# DAC_Output.net
KiCad netlist of a schematic drawn in Altium Designer
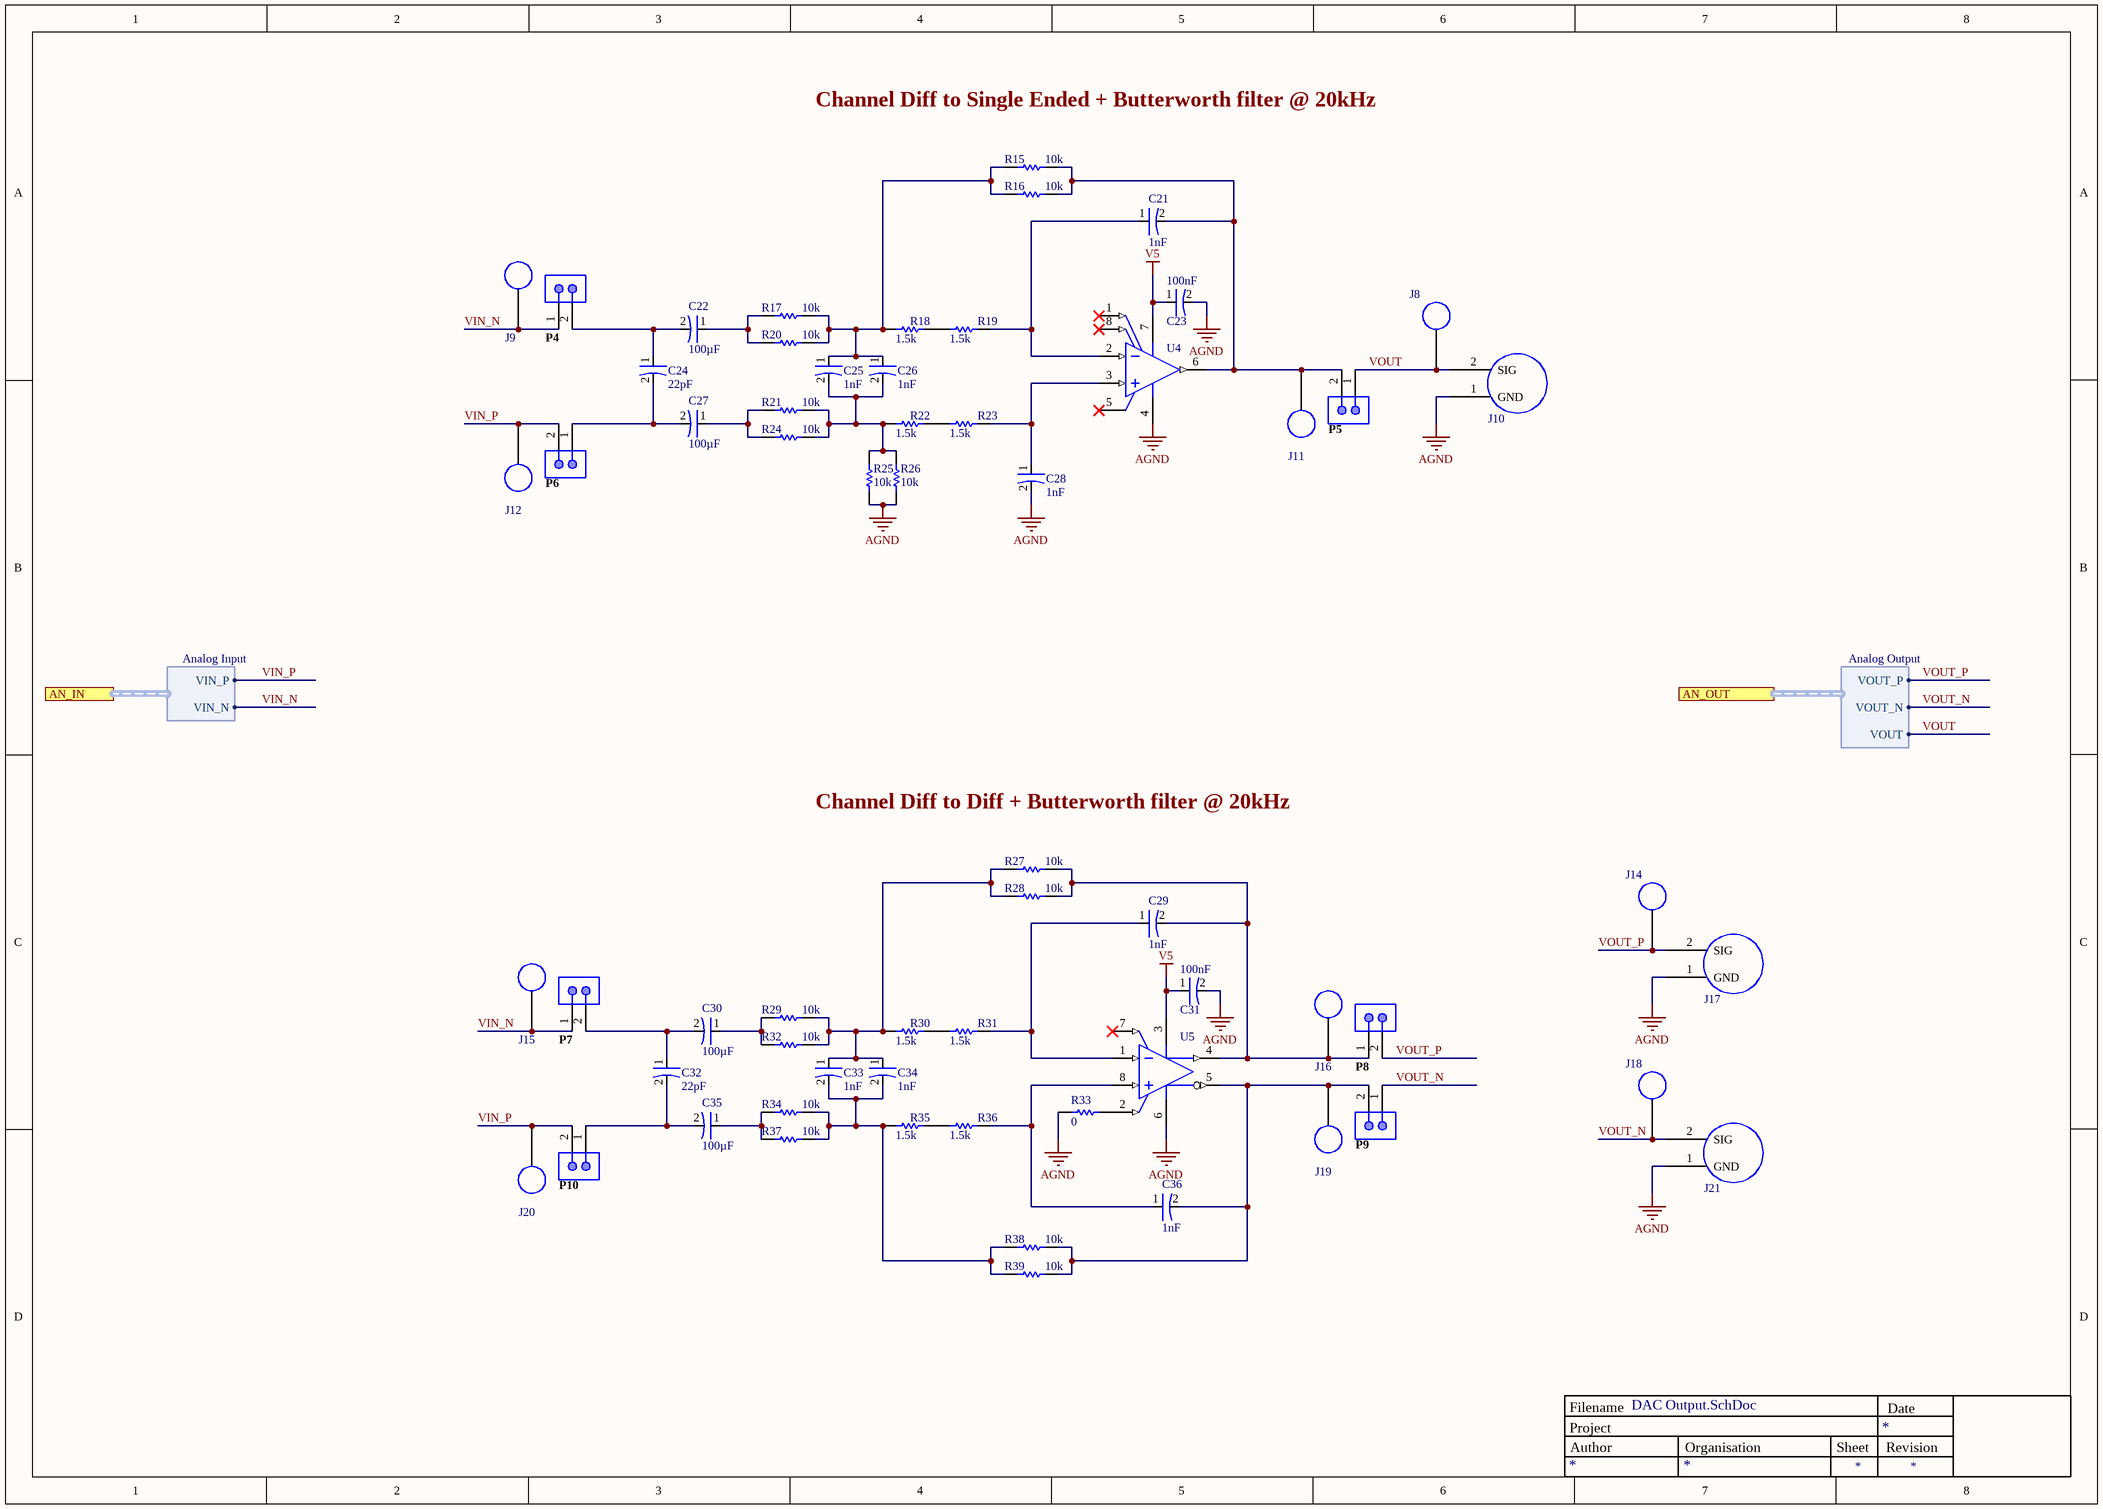
[diagram p0: DAC Output.SchDoc]

(export (version "E")
  (design (tool "Eeschema 10.0.6"))
  (components
    (comp (ref "C21")
      (value "1nF")
      (footprint "0402-M")
      (description "CAP-1nF-CER-0402-50V-X5R-10%")
      (fields (field (name "MANUFACTURER") "Generic") (field (name "Comment") "CAP 1nF CER 0402 50V X5R 10%"))
      (libsource (lib "") (part "Symbol_1"))
    )
    (comp (ref "C22")
      (value "100µF")
      (footprint "1210-M")
      (description "CAP-100uF-CER-1210-16V-X5R-20%")
      (fields
        (field (name "MANUFACTURER") "Generic")
        (field (name "Comment") "CAP 100uF CER 1210 16V X5R 20%")
      )
      (libsource (lib "") (part "Symbol_1"))
    )
    (comp (ref "C23")
      (value "100nF")
      (footprint "0805-M")
      (description "CAP-0.1uF-CER-0805-50V- X7R-5%")
      (fields
        (field (name "MANUFACTURER") "Generic")
        (field (name "Comment") "CAP 0.1uF CER 0805 50V  X7R 5%")
      )
      (libsource (lib "") (part "Symbol_1"))
    )
    (comp (ref "C24")
      (value "22pF")
      (footprint "0805-M")
      (description "CAP 22pF CER 0805 50V C0G 2%")
      (fields (field (name "MANUFACTURER") "Generic"))
      (libsource (lib "") (part "Symbol_1"))
    )
    (comp (ref "C25")
      (value "1nF")
      (footprint "0402-M")
      (description "CAP-1nF-CER-0402-50V-X5R-10%")
      (fields (field (name "MANUFACTURER") "Generic") (field (name "Comment") "CAP 1nF CER 0402 50V X5R 10%"))
      (libsource (lib "") (part "Symbol_1"))
    )
    (comp (ref "C26")
      (value "1nF")
      (footprint "0402-M")
      (description "CAP-1nF-CER-0402-50V-X5R-10%")
      (fields (field (name "MANUFACTURER") "Generic") (field (name "Comment") "CAP 1nF CER 0402 50V X5R 10%"))
      (libsource (lib "") (part "Symbol_1"))
    )
    (comp (ref "C27")
      (value "100µF")
      (footprint "1210-M")
      (description "CAP-100uF-CER-1210-16V-X5R-20%")
      (fields
        (field (name "MANUFACTURER") "Generic")
        (field (name "Comment") "CAP 100uF CER 1210 16V X5R 20%")
      )
      (libsource (lib "") (part "Symbol_1"))
    )
    (comp (ref "C28")
      (value "1nF")
      (footprint "0402-M")
      (description "CAP-1nF-CER-0402-50V-X5R-10%")
      (fields (field (name "MANUFACTURER") "Generic") (field (name "Comment") "CAP 1nF CER 0402 50V X5R 10%"))
      (libsource (lib "") (part "Symbol_1"))
    )
    (comp (ref "C29")
      (value "1nF")
      (footprint "0402-M")
      (description "CAP-1nF-CER-0402-50V-X5R-10%")
      (fields (field (name "MANUFACTURER") "Generic") (field (name "Comment") "CAP 1nF CER 0402 50V X5R 10%"))
      (libsource (lib "") (part "Symbol_1"))
    )
    (comp (ref "C30")
      (value "100µF")
      (footprint "1210-M")
      (description "CAP-100uF-CER-1210-16V-X5R-20%")
      (fields
        (field (name "MANUFACTURER") "Generic")
        (field (name "Comment") "CAP 100uF CER 1210 16V X5R 20%")
      )
      (libsource (lib "") (part "Symbol_1"))
    )
    (comp (ref "C31")
      (value "100nF")
      (footprint "0805-M")
      (description "CAP-0.1uF-CER-0805-50V- X7R-5%")
      (fields
        (field (name "MANUFACTURER") "Generic")
        (field (name "Comment") "CAP 0.1uF CER 0805 50V  X7R 5%")
      )
      (libsource (lib "") (part "Symbol_1"))
    )
    (comp (ref "C32")
      (value "22pF")
      (footprint "0805-M")
      (description "CAP 22pF CER 0805 50V C0G 2%")
      (fields (field (name "MANUFACTURER") "Generic"))
      (libsource (lib "") (part "Symbol_1"))
    )
    (comp (ref "C33")
      (value "1nF")
      (footprint "0402-M")
      (description "CAP-1nF-CER-0402-50V-X5R-10%")
      (fields (field (name "MANUFACTURER") "Generic") (field (name "Comment") "CAP 1nF CER 0402 50V X5R 10%"))
      (libsource (lib "") (part "Symbol_1"))
    )
    (comp (ref "C34")
      (value "1nF")
      (footprint "0402-M")
      (description "CAP-1nF-CER-0402-50V-X5R-10%")
      (fields (field (name "MANUFACTURER") "Generic") (field (name "Comment") "CAP 1nF CER 0402 50V X5R 10%"))
      (libsource (lib "") (part "Symbol_1"))
    )
    (comp (ref "C35")
      (value "100µF")
      (footprint "1210-M")
      (description "CAP-100uF-CER-1210-16V-X5R-20%")
      (fields
        (field (name "MANUFACTURER") "Generic")
        (field (name "Comment") "CAP 100uF CER 1210 16V X5R 20%")
      )
      (libsource (lib "") (part "Symbol_1"))
    )
    (comp (ref "C36")
      (value "1nF")
      (footprint "0402-M")
      (description "CAP-1nF-CER-0402-50V-X5R-10%")
      (fields (field (name "MANUFACTURER") "Generic") (field (name "Comment") "CAP 1nF CER 0402 50V X5R 10%"))
      (libsource (lib "") (part "Symbol_1"))
    )
    (comp (ref "J8")
      (value "151-203-RC")
      (footprint "151-203-RC-Footprint-1")
      (description "PCB-Probe-Ring")
      (libsource (lib "University of Malta - MEMENTO") (part "PCB Probe Ring"))
    )
    (comp (ref "J9")
      (value "151-203-RC")
      (footprint "151-203-RC-Footprint-1")
      (description "PCB-Probe-Ring")
      (libsource (lib "University of Malta - MEMENTO") (part "PCB Probe Ring"))
    )
    (comp (ref "J10")
      (value "SMA CONNECTOR")
      (footprint "SMA CONNECTOR-Footprint-1")
      (fields (field (name "MANUFACTURER") "LPRS"))
      (libsource (lib "University of Malta - MEMENTO") (part "SMA CONNECTOR"))
    )
    (comp (ref "J11")
      (value "151-203-RC")
      (footprint "151-203-RC-Footprint-1")
      (description "PCB-Probe-Ring")
      (libsource (lib "University of Malta - MEMENTO") (part "PCB Probe Ring"))
    )
    (comp (ref "J12")
      (value "151-203-RC")
      (footprint "151-203-RC-Footprint-1")
      (description "PCB-Probe-Ring")
      (libsource (lib "University of Malta - MEMENTO") (part "PCB Probe Ring"))
    )
    (comp (ref "J14")
      (value "151-203-RC")
      (footprint "151-203-RC-Footprint-1")
      (description "PCB-Probe-Ring")
      (libsource (lib "University of Malta - MEMENTO") (part "PCB Probe Ring"))
    )
    (comp (ref "J15")
      (value "151-203-RC")
      (footprint "151-203-RC-Footprint-1")
      (description "PCB-Probe-Ring")
      (libsource (lib "University of Malta - MEMENTO") (part "PCB Probe Ring"))
    )
    (comp (ref "J16")
      (value "151-203-RC")
      (footprint "151-203-RC-Footprint-1")
      (description "PCB-Probe-Ring")
      (libsource (lib "University of Malta - MEMENTO") (part "PCB Probe Ring"))
    )
    (comp (ref "J17")
      (value "SMA CONNECTOR")
      (footprint "SMA CONNECTOR-Footprint-1")
      (fields (field (name "MANUFACTURER") "LPRS"))
      (libsource (lib "University of Malta - MEMENTO") (part "SMA CONNECTOR"))
    )
    (comp (ref "J18")
      (value "151-203-RC")
      (footprint "151-203-RC-Footprint-1")
      (description "PCB-Probe-Ring")
      (libsource (lib "University of Malta - MEMENTO") (part "PCB Probe Ring"))
    )
    (comp (ref "J19")
      (value "151-203-RC")
      (footprint "151-203-RC-Footprint-1")
      (description "PCB-Probe-Ring")
      (libsource (lib "University of Malta - MEMENTO") (part "PCB Probe Ring"))
    )
    (comp (ref "J20")
      (value "151-203-RC")
      (footprint "151-203-RC-Footprint-1")
      (description "PCB-Probe-Ring")
      (libsource (lib "University of Malta - MEMENTO") (part "PCB Probe Ring"))
    )
    (comp (ref "J21")
      (value "SMA CONNECTOR")
      (footprint "SMA CONNECTOR-Footprint-1")
      (fields (field (name "MANUFACTURER") "LPRS"))
      (libsource (lib "University of Malta - MEMENTO") (part "SMA CONNECTOR"))
    )
    (comp (ref "P4")
      (value "GENERIC 2PIN HEADER MALE")
      (footprint "GENERIC 2PIN HEADER 0")
      (description "CONN MAL TH 2 0Deg HEADER")
      (fields (field (name "MANUFACTURER") "Generic"))
      (libsource (lib "") (part "GENERIC 2PIN HEADER MALE_1"))
    )
    (comp (ref "P5")
      (value "GENERIC 2PIN HEADER MALE")
      (footprint "GENERIC 2PIN HEADER 0")
      (description "CONN MAL TH 2 0Deg HEADER")
      (fields (field (name "MANUFACTURER") "Generic"))
      (libsource (lib "University of Malta - MEMENTO") (part "GENERIC 2PIN HEADER MALE"))
    )
    (comp (ref "P6")
      (value "GENERIC 2PIN HEADER MALE")
      (footprint "GENERIC 2PIN HEADER 0")
      (description "CONN MAL TH 2 0Deg HEADER")
      (fields (field (name "MANUFACTURER") "Generic"))
      (libsource (lib "University of Malta - MEMENTO") (part "GENERIC 2PIN HEADER MALE"))
    )
    (comp (ref "P7")
      (value "GENERIC 2PIN HEADER MALE")
      (footprint "GENERIC 2PIN HEADER 0")
      (description "CONN MAL TH 2 0Deg HEADER")
      (fields (field (name "MANUFACTURER") "Generic"))
      (libsource (lib "") (part "GENERIC 2PIN HEADER MALE_1"))
    )
    (comp (ref "P8")
      (value "GENERIC 2PIN HEADER MALE")
      (footprint "GENERIC 2PIN HEADER 0")
      (description "CONN MAL TH 2 0Deg HEADER")
      (fields (field (name "MANUFACTURER") "Generic"))
      (libsource (lib "") (part "GENERIC 2PIN HEADER MALE_1"))
    )
    (comp (ref "P9")
      (value "GENERIC 2PIN HEADER MALE")
      (footprint "GENERIC 2PIN HEADER 0")
      (description "CONN MAL TH 2 0Deg HEADER")
      (fields (field (name "MANUFACTURER") "Generic"))
      (libsource (lib "University of Malta - MEMENTO") (part "GENERIC 2PIN HEADER MALE"))
    )
    (comp (ref "P10")
      (value "GENERIC 2PIN HEADER MALE")
      (footprint "GENERIC 2PIN HEADER 0")
      (description "CONN MAL TH 2 0Deg HEADER")
      (fields (field (name "MANUFACTURER") "Generic"))
      (libsource (lib "University of Malta - MEMENTO") (part "GENERIC 2PIN HEADER MALE"))
    )
    (comp (ref "R15")
      (value "10k")
      (footprint "0805-M")
      (description "RES-10k-0805-125mW-1%")
      (fields (field (name "MANUFACTURER") "Generic") (field (name "Comment") "RES 10k 0805 125mW 1%"))
      (libsource (lib "University of Malta - MEMENTO") (part "Symbol"))
    )
    (comp (ref "R16")
      (value "10k")
      (footprint "0805-M")
      (description "RES-10k-0805-125mW-1%")
      (fields (field (name "MANUFACTURER") "Generic") (field (name "Comment") "RES 10k 0805 125mW 1%"))
      (libsource (lib "University of Malta - MEMENTO") (part "Symbol"))
    )
    (comp (ref "R17")
      (value "10k")
      (footprint "0805-M")
      (description "RES-10k-0805-125mW-1%")
      (fields (field (name "MANUFACTURER") "Generic") (field (name "Comment") "RES 10k 0805 125mW 1%"))
      (libsource (lib "University of Malta - MEMENTO") (part "Symbol"))
    )
    (comp (ref "R18")
      (value "1.5k")
      (footprint "0402-M")
      (description "RES-1.5k-0402-63mW-5%")
      (fields (field (name "MANUFACTURER") "Generic") (field (name "Comment") "RES 1.5k 0402 63mW 5%"))
      (libsource (lib "University of Malta - MEMENTO") (part "Symbol"))
    )
    (comp (ref "R19")
      (value "1.5k")
      (footprint "0402-M")
      (description "RES-1.5k-0402-63mW-5%")
      (fields (field (name "MANUFACTURER") "Generic") (field (name "Comment") "RES 1.5k 0402 63mW 5%"))
      (libsource (lib "University of Malta - MEMENTO") (part "Symbol"))
    )
    (comp (ref "R20")
      (value "10k")
      (footprint "0805-M")
      (description "RES-10k-0805-125mW-1%")
      (fields (field (name "MANUFACTURER") "Generic") (field (name "Comment") "RES 10k 0805 125mW 1%"))
      (libsource (lib "University of Malta - MEMENTO") (part "Symbol"))
    )
    (comp (ref "R21")
      (value "10k")
      (footprint "0805-M")
      (description "RES-10k-0805-125mW-1%")
      (fields (field (name "MANUFACTURER") "Generic") (field (name "Comment") "RES 10k 0805 125mW 1%"))
      (libsource (lib "University of Malta - MEMENTO") (part "Symbol"))
    )
    (comp (ref "R22")
      (value "1.5k")
      (footprint "0402-M")
      (description "RES-1.5k-0402-63mW-5%")
      (fields (field (name "MANUFACTURER") "Generic") (field (name "Comment") "RES 1.5k 0402 63mW 5%"))
      (libsource (lib "University of Malta - MEMENTO") (part "Symbol"))
    )
    (comp (ref "R23")
      (value "1.5k")
      (footprint "0402-M")
      (description "RES-1.5k-0402-63mW-5%")
      (fields (field (name "MANUFACTURER") "Generic") (field (name "Comment") "RES 1.5k 0402 63mW 5%"))
      (libsource (lib "University of Malta - MEMENTO") (part "Symbol"))
    )
    (comp (ref "R24")
      (value "10k")
      (footprint "0805-M")
      (description "RES-10k-0805-125mW-1%")
      (fields (field (name "MANUFACTURER") "Generic") (field (name "Comment") "RES 10k 0805 125mW 1%"))
      (libsource (lib "University of Malta - MEMENTO") (part "Symbol"))
    )
    (comp (ref "R25")
      (value "10k")
      (footprint "0805-M")
      (description "RES-10k-0805-125mW-1%")
      (fields (field (name "MANUFACTURER") "Generic") (field (name "Comment") "RES 10k 0805 125mW 1%"))
      (libsource (lib "University of Malta - MEMENTO") (part "Symbol"))
    )
    (comp (ref "R26")
      (value "10k")
      (footprint "0805-M")
      (description "RES-10k-0805-125mW-1%")
      (fields (field (name "MANUFACTURER") "Generic") (field (name "Comment") "RES 10k 0805 125mW 1%"))
      (libsource (lib "University of Malta - MEMENTO") (part "Symbol"))
    )
    (comp (ref "R27")
      (value "10k")
      (footprint "0805-M")
      (description "RES-10k-0805-125mW-1%")
      (fields (field (name "MANUFACTURER") "Generic") (field (name "Comment") "RES 10k 0805 125mW 1%"))
      (libsource (lib "University of Malta - MEMENTO") (part "Symbol"))
    )
    (comp (ref "R28")
      (value "10k")
      (footprint "0805-M")
      (description "RES-10k-0805-125mW-1%")
      (fields (field (name "MANUFACTURER") "Generic") (field (name "Comment") "RES 10k 0805 125mW 1%"))
      (libsource (lib "University of Malta - MEMENTO") (part "Symbol"))
    )
    (comp (ref "R29")
      (value "10k")
      (footprint "0805-M")
      (description "RES-10k-0805-125mW-1%")
      (fields (field (name "MANUFACTURER") "Generic") (field (name "Comment") "RES 10k 0805 125mW 1%"))
      (libsource (lib "University of Malta - MEMENTO") (part "Symbol"))
    )
    (comp (ref "R30")
      (value "1.5k")
      (footprint "0402-M")
      (description "RES-1.5k-0402-63mW-5%")
      (fields (field (name "MANUFACTURER") "Generic") (field (name "Comment") "RES 1.5k 0402 63mW 5%"))
      (libsource (lib "University of Malta - MEMENTO") (part "Symbol"))
    )
    (comp (ref "R31")
      (value "1.5k")
      (footprint "0402-M")
      (description "RES-1.5k-0402-63mW-5%")
      (fields (field (name "MANUFACTURER") "Generic") (field (name "Comment") "RES 1.5k 0402 63mW 5%"))
      (libsource (lib "University of Malta - MEMENTO") (part "Symbol"))
    )
    (comp (ref "R32")
      (value "10k")
      (footprint "0805-M")
      (description "RES-10k-0805-125mW-1%")
      (fields (field (name "MANUFACTURER") "Generic") (field (name "Comment") "RES 10k 0805 125mW 1%"))
      (libsource (lib "University of Malta - MEMENTO") (part "Symbol"))
    )
    (comp (ref "R33")
      (value "0")
      (footprint "0402-M")
      (description "RES-0-0402-63mW-5%")
      (fields (field (name "MANUFACTURER") "Generic") (field (name "Comment") "RES 0 0402 63mW"))
      (libsource (lib "University of Malta - MEMENTO") (part "Symbol"))
    )
    (comp (ref "R34")
      (value "10k")
      (footprint "0805-M")
      (description "RES-10k-0805-125mW-1%")
      (fields (field (name "MANUFACTURER") "Generic") (field (name "Comment") "RES 10k 0805 125mW 1%"))
      (libsource (lib "University of Malta - MEMENTO") (part "Symbol"))
    )
    (comp (ref "R35")
      (value "1.5k")
      (footprint "0402-M")
      (description "RES-1.5k-0402-63mW-5%")
      (fields (field (name "MANUFACTURER") "Generic") (field (name "Comment") "RES 1.5k 0402 63mW 5%"))
      (libsource (lib "University of Malta - MEMENTO") (part "Symbol"))
    )
    (comp (ref "R36")
      (value "1.5k")
      (footprint "0402-M")
      (description "RES-1.5k-0402-63mW-5%")
      (fields (field (name "MANUFACTURER") "Generic") (field (name "Comment") "RES 1.5k 0402 63mW 5%"))
      (libsource (lib "University of Malta - MEMENTO") (part "Symbol"))
    )
    (comp (ref "R37")
      (value "10k")
      (footprint "0805-M")
      (description "RES-10k-0805-125mW-1%")
      (fields (field (name "MANUFACTURER") "Generic") (field (name "Comment") "RES 10k 0805 125mW 1%"))
      (libsource (lib "University of Malta - MEMENTO") (part "Symbol"))
    )
    (comp (ref "R38")
      (value "10k")
      (footprint "0805-M")
      (description "RES-10k-0805-125mW-1%")
      (fields (field (name "MANUFACTURER") "Generic") (field (name "Comment") "RES 10k 0805 125mW 1%"))
      (libsource (lib "University of Malta - MEMENTO") (part "Symbol"))
    )
    (comp (ref "R39")
      (value "10k")
      (footprint "0805-M")
      (description "RES-10k-0805-125mW-1%")
      (fields (field (name "MANUFACTURER") "Generic") (field (name "Comment") "RES 10k 0805 125mW 1%"))
      (libsource (lib "University of Malta - MEMENTO") (part "Symbol"))
    )
    (comp (ref "U4")
      (value "OPA227UA/2K5")
      (footprint "D0008A_L")
      (description "IC OPAMP GP 8MHZ 8SOIC")
      (libsource (lib "University of Malta - MEMENTO") (part "TI-OPA227-8"))
    )
    (comp (ref "U5")
      (value "OPA1632DR")
      (footprint "D0008A_L")
      (description "IC OPAMP AUDIO 180MHZ 8SOIC")
      (libsource (lib "University of Malta - MEMENTO") (part "TI-OPA1632D8"))
    )
  )
  (nets
    (net (code "4") (name "/VIN_N") (class "Default")
      (node (ref "J15") (pin "1") (pinfunction "1_1") (pintype "passive"))
      (node (ref "J9") (pin "1") (pinfunction "1_1") (pintype "passive"))
      (node (ref "P4") (pin "1") (pinfunction "1_1") (pintype "passive"))
      (node (ref "P7") (pin "1") (pinfunction "1_1") (pintype "passive"))
    )
    (net (code "5") (name "/VIN_P") (class "Default")
      (node (ref "J12") (pin "1") (pinfunction "1_1") (pintype "passive"))
      (node (ref "J20") (pin "1") (pinfunction "1_1") (pintype "passive"))
      (node (ref "P10") (pin "2") (pinfunction "2_2") (pintype "passive"))
      (node (ref "P6") (pin "2") (pinfunction "2_2") (pintype "passive"))
    )
    (net (code "6") (name "/VOUT") (class "Default")
      (node (ref "J10") (pin "2") (pinfunction "SIG_2") (pintype "passive"))
      (node (ref "J8") (pin "1") (pinfunction "1_1") (pintype "passive"))
      (node (ref "P5") (pin "1") (pinfunction "1_1") (pintype "passive"))
    )
    (net (code "7") (name "/VOUT_N") (class "Default")
      (node (ref "J18") (pin "1") (pinfunction "1_1") (pintype "passive"))
      (node (ref "J21") (pin "2") (pinfunction "SIG_2") (pintype "passive"))
      (node (ref "P9") (pin "1") (pinfunction "1_1") (pintype "passive"))
    )
    (net (code "8") (name "/VOUT_P") (class "Default")
      (node (ref "J14") (pin "1") (pinfunction "1_1") (pintype "passive"))
      (node (ref "J17") (pin "2") (pinfunction "SIG_2") (pintype "passive"))
      (node (ref "P8") (pin "2") (pinfunction "2_2") (pintype "passive"))
    )
    (net (code "11") (name "AGND") (class "Default")
      (node (ref "C23") (pin "2") (pinfunction "Cathode_2") (pintype "passive"))
      (node (ref "C28") (pin "2") (pinfunction "Cathode_2") (pintype "passive"))
      (node (ref "C31") (pin "2") (pinfunction "Cathode_2") (pintype "passive"))
      (node (ref "J10") (pin "1") (pinfunction "GND_1") (pintype "passive"))
      (node (ref "J17") (pin "1") (pinfunction "GND_1") (pintype "passive"))
      (node (ref "J21") (pin "1") (pinfunction "GND_1") (pintype "passive"))
      (node (ref "R25") (pin "1") (pinfunction "1_1") (pintype "passive"))
      (node (ref "R26") (pin "1") (pinfunction "1_1") (pintype "passive"))
      (node (ref "R33") (pin "1") (pinfunction "1_1") (pintype "passive"))
      (node (ref "U4") (pin "4") (pinfunction "V-_4") (pintype "power_in"))
      (node (ref "U5") (pin "6") (pinfunction "V-_6") (pintype "power_in"))
    )
    (net (code "12") (name "Net-(C21-Anode)") (class "Default")
      (node (ref "C21") (pin "1") (pinfunction "Anode_1") (pintype "passive"))
      (node (ref "R19") (pin "2") (pinfunction "2_2") (pintype "passive"))
      (node (ref "U4") (pin "2") (pinfunction "IN-_2") (pintype "input"))
    )
    (net (code "13") (name "Net-(C21-Cathode)") (class "Default")
      (node (ref "C21") (pin "2") (pinfunction "Cathode_2") (pintype "passive"))
      (node (ref "J11") (pin "1") (pinfunction "1_1") (pintype "passive"))
      (node (ref "P5") (pin "2") (pinfunction "2_2") (pintype "passive"))
      (node (ref "R15") (pin "2") (pinfunction "2_2") (pintype "passive"))
      (node (ref "R16") (pin "2") (pinfunction "2_2") (pintype "passive"))
      (node (ref "U4") (pin "6") (pinfunction "OUT_6") (pintype "output"))
    )
    (net (code "14") (name "Net-(C22-Anode)") (class "Default")
      (node (ref "C22") (pin "1") (pinfunction "Anode_1") (pintype "passive"))
      (node (ref "R17") (pin "1") (pinfunction "1_1") (pintype "passive"))
      (node (ref "R20") (pin "1") (pinfunction "1_1") (pintype "passive"))
    )
    (net (code "15") (name "Net-(C22-Cathode)") (class "Default")
      (node (ref "C22") (pin "2") (pinfunction "Cathode_2") (pintype "passive"))
      (node (ref "C24") (pin "1") (pinfunction "Anode_1") (pintype "passive"))
      (node (ref "P4") (pin "2") (pinfunction "2_2") (pintype "passive"))
    )
    (net (code "16") (name "Net-(C24-Cathode)") (class "Default")
      (node (ref "C24") (pin "2") (pinfunction "Cathode_2") (pintype "passive"))
      (node (ref "C27") (pin "2") (pinfunction "Cathode_2") (pintype "passive"))
      (node (ref "P6") (pin "1") (pinfunction "1_1") (pintype "passive"))
    )
    (net (code "17") (name "Net-(C25-Anode)") (class "Default")
      (node (ref "C25") (pin "1") (pinfunction "Anode_1") (pintype "passive"))
      (node (ref "C26") (pin "1") (pinfunction "Anode_1") (pintype "passive"))
      (node (ref "R15") (pin "1") (pinfunction "1_1") (pintype "passive"))
      (node (ref "R16") (pin "1") (pinfunction "1_1") (pintype "passive"))
      (node (ref "R17") (pin "2") (pinfunction "2_2") (pintype "passive"))
      (node (ref "R18") (pin "1") (pinfunction "1_1") (pintype "passive"))
      (node (ref "R20") (pin "2") (pinfunction "2_2") (pintype "passive"))
    )
    (net (code "18") (name "Net-(C25-Cathode)") (class "Default")
      (node (ref "C25") (pin "2") (pinfunction "Cathode_2") (pintype "passive"))
      (node (ref "C26") (pin "2") (pinfunction "Cathode_2") (pintype "passive"))
      (node (ref "R21") (pin "2") (pinfunction "2_2") (pintype "passive"))
      (node (ref "R22") (pin "1") (pinfunction "1_1") (pintype "passive"))
      (node (ref "R24") (pin "2") (pinfunction "2_2") (pintype "passive"))
      (node (ref "R25") (pin "2") (pinfunction "2_2") (pintype "passive"))
      (node (ref "R26") (pin "2") (pinfunction "2_2") (pintype "passive"))
    )
    (net (code "19") (name "Net-(C27-Anode)") (class "Default")
      (node (ref "C27") (pin "1") (pinfunction "Anode_1") (pintype "passive"))
      (node (ref "R21") (pin "1") (pinfunction "1_1") (pintype "passive"))
      (node (ref "R24") (pin "1") (pinfunction "1_1") (pintype "passive"))
    )
    (net (code "20") (name "Net-(C28-Anode)") (class "Default")
      (node (ref "C28") (pin "1") (pinfunction "Anode_1") (pintype "passive"))
      (node (ref "R23") (pin "2") (pinfunction "2_2") (pintype "passive"))
      (node (ref "U4") (pin "3") (pinfunction "IN+_3") (pintype "input"))
    )
    (net (code "21") (name "Net-(C29-Anode)") (class "Default")
      (node (ref "C29") (pin "1") (pinfunction "Anode_1") (pintype "passive"))
      (node (ref "R31") (pin "2") (pinfunction "2_2") (pintype "passive"))
      (node (ref "U5") (pin "1") (pinfunction "VIN-_1") (pintype "input"))
    )
    (net (code "22") (name "Net-(C29-Cathode)") (class "Default")
      (node (ref "C29") (pin "2") (pinfunction "Cathode_2") (pintype "passive"))
      (node (ref "J16") (pin "1") (pinfunction "1_1") (pintype "passive"))
      (node (ref "P8") (pin "1") (pinfunction "1_1") (pintype "passive"))
      (node (ref "R27") (pin "2") (pinfunction "2_2") (pintype "passive"))
      (node (ref "R28") (pin "2") (pinfunction "2_2") (pintype "passive"))
      (node (ref "U5") (pin "4") (pinfunction "VOUT+_4") (pintype "output"))
    )
    (net (code "23") (name "Net-(C30-Anode)") (class "Default")
      (node (ref "C30") (pin "1") (pinfunction "Anode_1") (pintype "passive"))
      (node (ref "R29") (pin "1") (pinfunction "1_1") (pintype "passive"))
      (node (ref "R32") (pin "1") (pinfunction "1_1") (pintype "passive"))
    )
    (net (code "24") (name "Net-(C30-Cathode)") (class "Default")
      (node (ref "C30") (pin "2") (pinfunction "Cathode_2") (pintype "passive"))
      (node (ref "C32") (pin "1") (pinfunction "Anode_1") (pintype "passive"))
      (node (ref "P7") (pin "2") (pinfunction "2_2") (pintype "passive"))
    )
    (net (code "25") (name "Net-(C32-Cathode)") (class "Default")
      (node (ref "C32") (pin "2") (pinfunction "Cathode_2") (pintype "passive"))
      (node (ref "C35") (pin "2") (pinfunction "Cathode_2") (pintype "passive"))
      (node (ref "P10") (pin "1") (pinfunction "1_1") (pintype "passive"))
    )
    (net (code "26") (name "Net-(C33-Anode)") (class "Default")
      (node (ref "C33") (pin "1") (pinfunction "Anode_1") (pintype "passive"))
      (node (ref "C34") (pin "1") (pinfunction "Anode_1") (pintype "passive"))
      (node (ref "R27") (pin "1") (pinfunction "1_1") (pintype "passive"))
      (node (ref "R28") (pin "1") (pinfunction "1_1") (pintype "passive"))
      (node (ref "R29") (pin "2") (pinfunction "2_2") (pintype "passive"))
      (node (ref "R30") (pin "1") (pinfunction "1_1") (pintype "passive"))
      (node (ref "R32") (pin "2") (pinfunction "2_2") (pintype "passive"))
    )
    (net (code "27") (name "Net-(C33-Cathode)") (class "Default")
      (node (ref "C33") (pin "2") (pinfunction "Cathode_2") (pintype "passive"))
      (node (ref "C34") (pin "2") (pinfunction "Cathode_2") (pintype "passive"))
      (node (ref "R34") (pin "2") (pinfunction "2_2") (pintype "passive"))
      (node (ref "R35") (pin "1") (pinfunction "1_1") (pintype "passive"))
      (node (ref "R37") (pin "2") (pinfunction "2_2") (pintype "passive"))
      (node (ref "R38") (pin "2") (pinfunction "2_2") (pintype "passive"))
      (node (ref "R39") (pin "2") (pinfunction "2_2") (pintype "passive"))
    )
    (net (code "28") (name "Net-(C35-Anode)") (class "Default")
      (node (ref "C35") (pin "1") (pinfunction "Anode_1") (pintype "passive"))
      (node (ref "R34") (pin "1") (pinfunction "1_1") (pintype "passive"))
      (node (ref "R37") (pin "1") (pinfunction "1_1") (pintype "passive"))
    )
    (net (code "29") (name "Net-(C36-Anode)") (class "Default")
      (node (ref "C36") (pin "1") (pinfunction "Anode_1") (pintype "passive"))
      (node (ref "R36") (pin "2") (pinfunction "2_2") (pintype "passive"))
      (node (ref "U5") (pin "8") (pinfunction "VIN+_8") (pintype "input"))
    )
    (net (code "30") (name "Net-(C36-Cathode)") (class "Default")
      (node (ref "C36") (pin "2") (pinfunction "Cathode_2") (pintype "passive"))
      (node (ref "J19") (pin "1") (pinfunction "1_1") (pintype "passive"))
      (node (ref "P9") (pin "2") (pinfunction "2_2") (pintype "passive"))
      (node (ref "R38") (pin "1") (pinfunction "1_1") (pintype "passive"))
      (node (ref "R39") (pin "1") (pinfunction "1_1") (pintype "passive"))
      (node (ref "U5") (pin "5") (pinfunction "VOUT-_5") (pintype "output"))
    )
    (net (code "31") (name "Net-(R18-Pad2)") (class "Default")
      (node (ref "R18") (pin "2") (pinfunction "2_2") (pintype "passive"))
      (node (ref "R19") (pin "1") (pinfunction "1_1") (pintype "passive"))
    )
    (net (code "32") (name "Net-(R22-Pad2)") (class "Default")
      (node (ref "R22") (pin "2") (pinfunction "2_2") (pintype "passive"))
      (node (ref "R23") (pin "1") (pinfunction "1_1") (pintype "passive"))
    )
    (net (code "33") (name "Net-(R30-Pad2)") (class "Default")
      (node (ref "R30") (pin "2") (pinfunction "2_2") (pintype "passive"))
      (node (ref "R31") (pin "1") (pinfunction "1_1") (pintype "passive"))
    )
    (net (code "34") (name "Net-(R35-Pad2)") (class "Default")
      (node (ref "R35") (pin "2") (pinfunction "2_2") (pintype "passive"))
      (node (ref "R36") (pin "1") (pinfunction "1_1") (pintype "passive"))
    )
    (net (code "35") (name "Net-(U5-VOCM)") (class "Default")
      (node (ref "R33") (pin "2") (pinfunction "2_2") (pintype "passive"))
      (node (ref "U5") (pin "2") (pinfunction "VOCM_2") (pintype "input"))
    )
    (net (code "36") (name "V5") (class "Default")
      (node (ref "C23") (pin "1") (pinfunction "Anode_1") (pintype "passive"))
      (node (ref "C31") (pin "1") (pinfunction "Anode_1") (pintype "passive"))
      (node (ref "U4") (pin "7") (pinfunction "V+_7") (pintype "power_in"))
      (node (ref "U5") (pin "3") (pinfunction "V+_3") (pintype "power_in"))
    )
    (net (code "37") (name "unconnected-(U4-NC-Pad5)") (class "Default")
      (node (ref "U4") (pin "5") (pinfunction "NC_5") (pintype "passive+no_connect"))
    )
    (net (code "38") (name "unconnected-(U4-TRIM-Pad1)") (class "Default")
      (node (ref "U4") (pin "1") (pinfunction "TRIM_1") (pintype "input+no_connect"))
    )
    (net (code "39") (name "unconnected-(U4-TRIM-Pad8)") (class "Default")
      (node (ref "U4") (pin "8") (pinfunction "TRIM_8") (pintype "input+no_connect"))
    )
    (net (code "40") (name "unconnected-(U5-ENABLE-Pad7)") (class "Default")
      (node (ref "U5") (pin "7") (pinfunction "ENABLE_7") (pintype "input+no_connect"))
    )
  )
)
